# Sheet1.net
KiCad netlist of a schematic drawn in Altium Designer
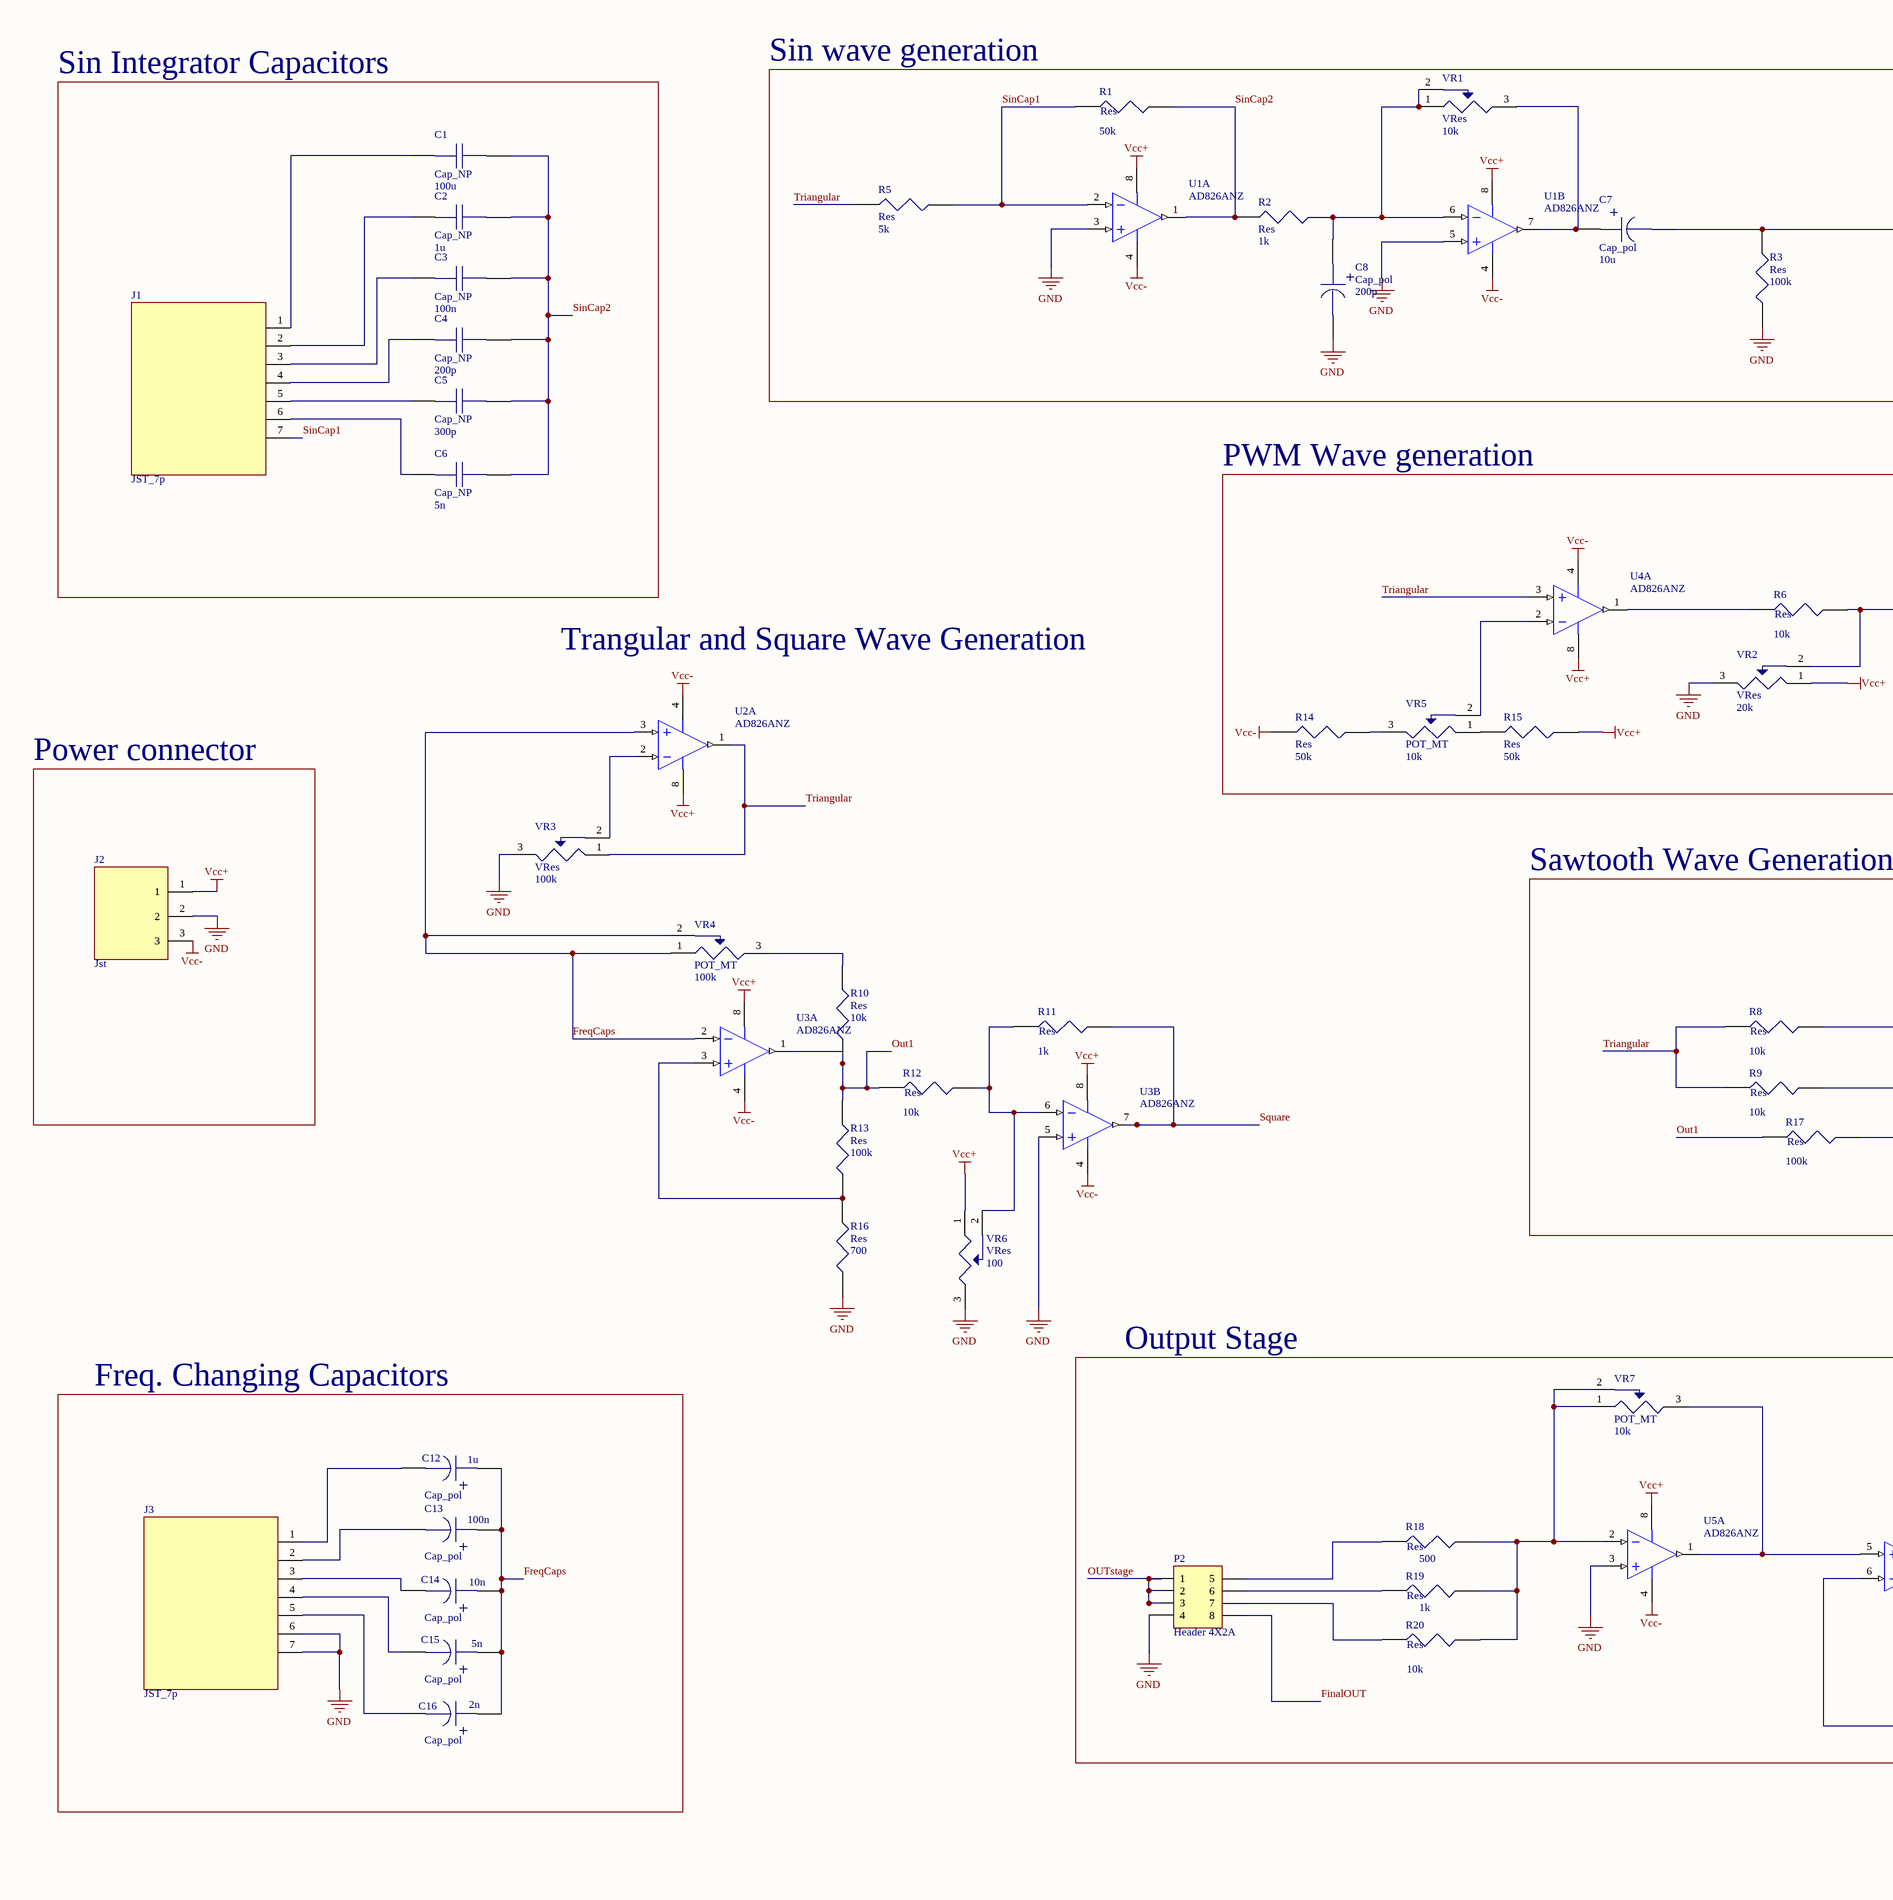
[diagram p0: Sheet1.SchDoc, left]
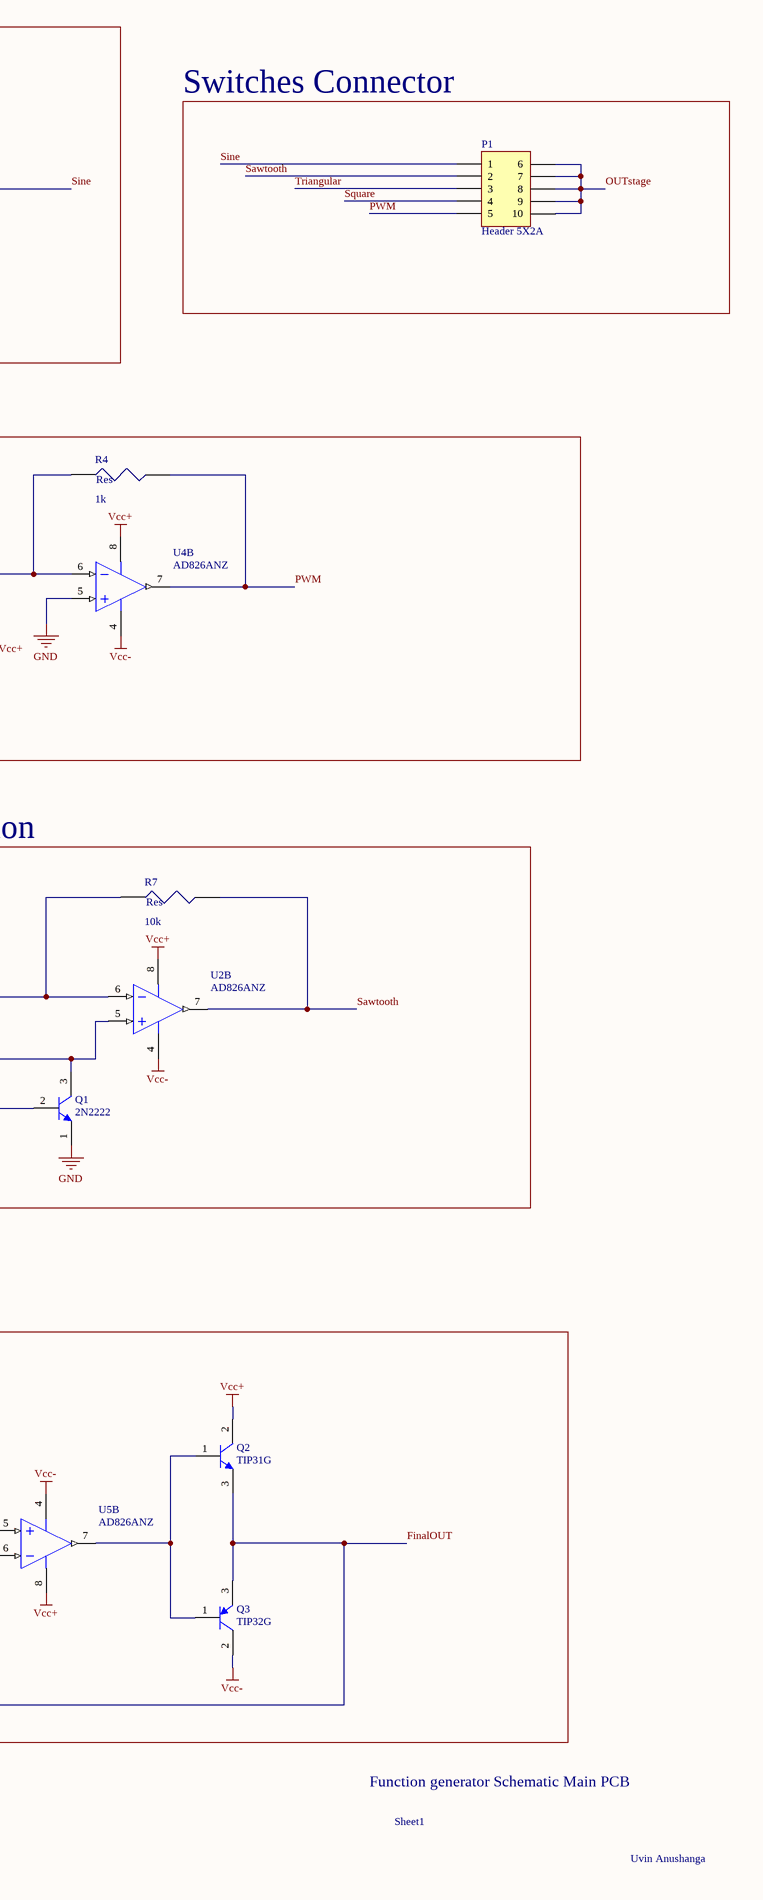
[diagram p1: Sheet1.SchDoc, right]

(export (version "E")
  (design (tool "Eeschema 10.0.6"))
  (components
    (comp (ref "C1")
      (value "Cap_NP")
      (footprint "Cap NP")
      (fields (field (name "ALTIUM_VALUE") "100u"))
      (libsource (lib "Funcgen") (part "Cap_NP"))
    )
    (comp (ref "C2")
      (value "Cap_NP")
      (footprint "Cap NP")
      (fields (field (name "ALTIUM_VALUE") "1u"))
      (libsource (lib "Funcgen") (part "Cap_NP"))
    )
    (comp (ref "C3")
      (value "Cap_NP")
      (footprint "Cap NP")
      (fields (field (name "ALTIUM_VALUE") "100n"))
      (libsource (lib "Funcgen") (part "Cap_NP"))
    )
    (comp (ref "C4")
      (value "Cap_NP")
      (footprint "Cap NP")
      (fields (field (name "ALTIUM_VALUE") "200p"))
      (libsource (lib "Funcgen") (part "Cap_NP"))
    )
    (comp (ref "C5")
      (value "Cap_NP")
      (footprint "Cap NP")
      (fields (field (name "ALTIUM_VALUE") "300p"))
      (libsource (lib "Funcgen") (part "Cap_NP"))
    )
    (comp (ref "C6")
      (value "Cap_NP")
      (footprint "Cap NP")
      (fields (field (name "ALTIUM_VALUE") "5n"))
      (libsource (lib "Funcgen") (part "Cap_NP"))
    )
    (comp (ref "C7")
      (value "Cap_pol")
      (footprint "Cap pol")
      (fields (field (name "ALTIUM_VALUE") "10u"))
      (libsource (lib "Schlib1") (part "Cap_pol"))
    )
    (comp (ref "C8")
      (value "Cap_pol")
      (footprint "Cap pol")
      (fields (field (name "ALTIUM_VALUE") "200p"))
      (libsource (lib "Schlib1") (part "Cap_pol"))
    )
    (comp (ref "C12")
      (value "Cap_pol")
      (footprint "Cap pol")
      (fields (field (name "ALTIUM_VALUE") "1u"))
      (libsource (lib "Schlib1") (part "Cap_pol"))
    )
    (comp (ref "C13")
      (value "Cap_pol")
      (footprint "Cap pol")
      (fields (field (name "ALTIUM_VALUE") "100n"))
      (libsource (lib "Schlib1") (part "Cap_pol"))
    )
    (comp (ref "C14")
      (value "Cap_pol")
      (footprint "Cap pol")
      (fields (field (name "ALTIUM_VALUE") "10n"))
      (libsource (lib "Schlib1") (part "Cap_pol"))
    )
    (comp (ref "C15")
      (value "Cap_pol")
      (footprint "Cap pol")
      (fields (field (name "ALTIUM_VALUE") "5n"))
      (libsource (lib "Schlib1") (part "Cap_pol"))
    )
    (comp (ref "C16")
      (value "Cap_pol")
      (footprint "Cap pol")
      (fields (field (name "ALTIUM_VALUE") "2n"))
      (libsource (lib "Schlib1") (part "Cap_pol"))
    )
    (comp (ref "J1") (value "JST_7p") (footprint "JST_7p") (libsource (lib "Funcgen") (part "JST_7p")))
    (comp (ref "J2") (value "Jst") (footprint "Jst_3p") (libsource (lib "Funcgen") (part "Jst_3p")))
    (comp (ref "J3") (value "JST_7p") (footprint "JST_7p") (libsource (lib "Funcgen") (part "JST_7p")))
    (comp (ref "P1")
      (value "Header 5X2A")
      (footprint "HDR2X5_CEN")
      (description "Header, 5-Pin, Dual row")
      (fields (field (name "PUBLISHER") "Altium Limited"))
      (libsource (lib "Miscellaneous Connectors") (part "Header 5X2A"))
    )
    (comp (ref "P2")
      (value "Header 4X2A")
      (footprint "HDR2X4_CEN")
      (description "Header, 4-Pin, Dual row")
      (fields (field (name "PUBLISHER") "Altium Limited"))
      (libsource (lib "Miscellaneous Connectors") (part "Header 4X2A"))
    )
    (comp (ref "Q1")
      (value "2N2222")
      (footprint "MLTC-TO-18-3")
      (description "Low Power Bipolar NPN Transistor, 30 V, -65 to 200 degC, 3-Pin TO-18, RoHS, Bulk")
      (fields (field (name "MANUFACTURER") "Multicomp"))
      (libsource (lib "Altium Content Vault") (part "BJT-NPN-EBC-3"))
    )
    (comp (ref "Q2")
      (value "TIP31G")
      (footprint "ONSC-TO-220-3-221A-09")
      (description "Complementary Silicon Plastic Power Transistor, 3-Pin TO-220, Pb-Free, Tube")
      (fields (field (name "MANUFACTURER") "On Semiconductor"))
      (libsource (lib "Altium Content Vault") (part "ONSC-NPN-B1C2E3-3_C"))
    )
    (comp (ref "Q3")
      (value "TIP32G")
      (footprint "ONSC-TO-220-3-221A-09")
      (description "Complementary Silicon Plastic Power Transistor, 3-Pin TO-220, Pb-Free, Tube")
      (fields (field (name "MANUFACTURER") "On Semiconductor"))
      (libsource (lib "Altium Content Vault") (part "ONSC-PNP-B1C2E3-3"))
    )
    (comp (ref "R1")
      (value "Res")
      (footprint "Res")
      (fields (field (name "ALTIUM_VALUE") "50k"))
      (libsource (lib "Funcgen") (part "Res"))
    )
    (comp (ref "R2")
      (value "Res")
      (footprint "Res")
      (fields (field (name "ALTIUM_VALUE") "1k"))
      (libsource (lib "Funcgen") (part "Res"))
    )
    (comp (ref "R3")
      (value "Res")
      (footprint "Res")
      (fields (field (name "ALTIUM_VALUE") "100k"))
      (libsource (lib "Funcgen") (part "Res"))
    )
    (comp (ref "R4")
      (value "Res")
      (footprint "Res")
      (fields (field (name "ALTIUM_VALUE") "1k"))
      (libsource (lib "Funcgen") (part "Res"))
    )
    (comp (ref "R5")
      (value "Res")
      (footprint "Res")
      (fields (field (name "ALTIUM_VALUE") "5k"))
      (libsource (lib "Funcgen") (part "Res"))
    )
    (comp (ref "R6")
      (value "Res")
      (footprint "Res")
      (fields (field (name "ALTIUM_VALUE") "10k"))
      (libsource (lib "Funcgen") (part "Res"))
    )
    (comp (ref "R7")
      (value "Res")
      (footprint "Res")
      (fields (field (name "ALTIUM_VALUE") "10k"))
      (libsource (lib "Funcgen") (part "Res"))
    )
    (comp (ref "R8")
      (value "Res")
      (footprint "Res")
      (fields (field (name "ALTIUM_VALUE") "10k"))
      (libsource (lib "Funcgen") (part "Res"))
    )
    (comp (ref "R9")
      (value "Res")
      (footprint "Res")
      (fields (field (name "ALTIUM_VALUE") "10k"))
      (libsource (lib "Funcgen") (part "Res"))
    )
    (comp (ref "R10")
      (value "Res")
      (footprint "Res")
      (fields (field (name "ALTIUM_VALUE") "10k"))
      (libsource (lib "Funcgen") (part "Res"))
    )
    (comp (ref "R11")
      (value "Res")
      (footprint "Res")
      (fields (field (name "ALTIUM_VALUE") "1k"))
      (libsource (lib "Funcgen") (part "Res"))
    )
    (comp (ref "R12")
      (value "Res")
      (footprint "Res")
      (fields (field (name "ALTIUM_VALUE") "10k"))
      (libsource (lib "Funcgen") (part "Res"))
    )
    (comp (ref "R13")
      (value "Res")
      (footprint "Res")
      (fields (field (name "ALTIUM_VALUE") "100k"))
      (libsource (lib "Funcgen") (part "Res"))
    )
    (comp (ref "R14")
      (value "Res")
      (footprint "Res")
      (fields (field (name "ALTIUM_VALUE") "50k"))
      (libsource (lib "Funcgen") (part "Res"))
    )
    (comp (ref "R15")
      (value "Res")
      (footprint "Res")
      (fields (field (name "ALTIUM_VALUE") "50k"))
      (libsource (lib "Funcgen") (part "Res"))
    )
    (comp (ref "R16")
      (value "Res")
      (footprint "Res")
      (fields (field (name "ALTIUM_VALUE") "700"))
      (libsource (lib "Funcgen") (part "Res"))
    )
    (comp (ref "R17")
      (value "Res")
      (footprint "Res")
      (fields (field (name "ALTIUM_VALUE") "100k"))
      (libsource (lib "Funcgen") (part "Res"))
    )
    (comp (ref "R18")
      (value "Res")
      (footprint "Res")
      (fields (field (name "ALTIUM_VALUE") "500"))
      (libsource (lib "Funcgen") (part "Res"))
    )
    (comp (ref "R19")
      (value "Res")
      (footprint "Res")
      (fields (field (name "ALTIUM_VALUE") "1k"))
      (libsource (lib "Funcgen") (part "Res"))
    )
    (comp (ref "R20")
      (value "Res")
      (footprint "Res")
      (fields (field (name "ALTIUM_VALUE") "10k"))
      (libsource (lib "Funcgen") (part "Res"))
    )
    (comp (ref "U1")
      (value "AD826ANZ")
      (footprint "ADI-N-8")
      (fields (field (name "MANUFACTURER") "Analog Devices") (field (name "GENERIC PART NUMBER") "AD826"))
      (libsource (lib "Altium Content Vault") (part "ADI-AD7xx_8xx-X-8"))
    )
    (comp (ref "U2")
      (value "AD826ANZ")
      (footprint "ADI-N-8")
      (fields (field (name "MANUFACTURER") "Analog Devices") (field (name "GENERIC PART NUMBER") "AD826"))
      (libsource (lib "Altium Content Vault") (part "ADI-AD7xx_8xx-X-8"))
    )
    (comp (ref "U3")
      (value "AD826ANZ")
      (footprint "ADI-N-8")
      (fields (field (name "MANUFACTURER") "Analog Devices") (field (name "GENERIC PART NUMBER") "AD826"))
      (libsource (lib "Altium Content Vault") (part "ADI-AD7xx_8xx-X-8"))
    )
    (comp (ref "U4")
      (value "AD826ANZ")
      (footprint "ADI-N-8")
      (fields (field (name "MANUFACTURER") "Analog Devices") (field (name "GENERIC PART NUMBER") "AD826"))
      (libsource (lib "Altium Content Vault") (part "ADI-AD7xx_8xx-X-8"))
    )
    (comp (ref "U5")
      (value "AD826ANZ")
      (footprint "ADI-N-8")
      (fields (field (name "MANUFACTURER") "Analog Devices") (field (name "GENERIC PART NUMBER") "AD826"))
      (libsource (lib "Altium Content Vault") (part "ADI-AD7xx_8xx-X-8"))
    )
    (comp (ref "VR1")
      (value "VRes")
      (footprint "VerRes")
      (fields (field (name "ALTIUM_VALUE") "10k"))
      (libsource (lib "Funcgen") (part "VRes"))
    )
    (comp (ref "VR2")
      (value "VRes")
      (footprint "VerRes")
      (fields (field (name "ALTIUM_VALUE") "20k"))
      (libsource (lib "Funcgen") (part "VRes"))
    )
    (comp (ref "VR3")
      (value "VRes")
      (footprint "VerRes")
      (fields (field (name "ALTIUM_VALUE") "100k"))
      (libsource (lib "Funcgen") (part "VRes"))
    )
    (comp (ref "VR4")
      (value "POT_MT")
      (footprint "POT MT")
      (fields (field (name "ALTIUM_VALUE") "100k"))
      (libsource (lib "Funcgen") (part "POT_MT"))
    )
    (comp (ref "VR5")
      (value "POT_MT")
      (footprint "POT MT")
      (fields (field (name "ALTIUM_VALUE") "10k"))
      (libsource (lib "Funcgen") (part "POT_MT"))
    )
    (comp (ref "VR6")
      (value "VRes")
      (footprint "VerRes")
      (fields (field (name "ALTIUM_VALUE") "100"))
      (libsource (lib "Funcgen") (part "VRes"))
    )
    (comp (ref "VR7")
      (value "POT_MT")
      (footprint "POT MT")
      (fields (field (name "ALTIUM_VALUE") "10k"))
      (libsource (lib "Funcgen") (part "POT_MT"))
    )
  )
  (nets
    (net (code "1") (name "/FinalOUT") (class "Default")
      (node (ref "P2") (pin "8") (pinfunction "8_8") (pintype "passive"))
      (node (ref "Q2") (pin "3") (pinfunction "E_3") (pintype "passive"))
      (node (ref "Q3") (pin "3") (pinfunction "E_3") (pintype "passive"))
      (node (ref "U5") (pin "6") (pinfunction "-IN_2_6") (pintype "input"))
    )
    (net (code "2") (name "/FreqCaps") (class "Default")
      (node (ref "C12") (pin "1") (pinfunction "1_1") (pintype "passive"))
      (node (ref "C13") (pin "1") (pinfunction "1_1") (pintype "passive"))
      (node (ref "C14") (pin "1") (pinfunction "1_1") (pintype "passive"))
      (node (ref "C15") (pin "1") (pinfunction "1_1") (pintype "passive"))
      (node (ref "C16") (pin "1") (pinfunction "1_1") (pintype "passive"))
      (node (ref "U2") (pin "3") (pinfunction "+IN_1_3") (pintype "input"))
      (node (ref "U3") (pin "2") (pinfunction "-IN_1_2") (pintype "input"))
      (node (ref "VR4") (pin "1") (pinfunction "1_1") (pintype "passive"))
      (node (ref "VR4") (pin "2") (pinfunction "2_2") (pintype "passive"))
    )
    (net (code "3") (name "/OUTstage") (class "Default")
      (node (ref "P1") (pin "10") (pinfunction "10_10") (pintype "passive"))
      (node (ref "P1") (pin "6") (pinfunction "6_6") (pintype "passive"))
      (node (ref "P1") (pin "7") (pinfunction "7_7") (pintype "passive"))
      (node (ref "P1") (pin "8") (pinfunction "8_8") (pintype "passive"))
      (node (ref "P1") (pin "9") (pinfunction "9_9") (pintype "passive"))
      (node (ref "P2") (pin "1") (pinfunction "1_1") (pintype "passive"))
      (node (ref "P2") (pin "2") (pinfunction "2_2") (pintype "passive"))
      (node (ref "P2") (pin "3") (pinfunction "3_3") (pintype "passive"))
    )
    (net (code "4") (name "/Out1") (class "Default")
      (node (ref "R10") (pin "2") (pinfunction "2_2") (pintype "passive"))
      (node (ref "R12") (pin "1") (pinfunction "1_1") (pintype "passive"))
      (node (ref "R13") (pin "1") (pinfunction "1_1") (pintype "passive"))
      (node (ref "R17") (pin "1") (pinfunction "1_1") (pintype "passive"))
      (node (ref "U3") (pin "1") (pinfunction "OUT_1_1") (pintype "output"))
    )
    (net (code "5") (name "/PWM") (class "Default")
      (node (ref "P1") (pin "5") (pinfunction "5_5") (pintype "passive"))
      (node (ref "R4") (pin "2") (pinfunction "2_2") (pintype "passive"))
      (node (ref "U4") (pin "7") (pinfunction "OUT_2_7") (pintype "output"))
    )
    (net (code "6") (name "/Sawtooth") (class "Default")
      (node (ref "P1") (pin "2") (pinfunction "2_2") (pintype "passive"))
      (node (ref "R7") (pin "2") (pinfunction "2_2") (pintype "passive"))
      (node (ref "U2") (pin "7") (pinfunction "OUT_2_7") (pintype "output"))
    )
    (net (code "7") (name "/SinCap1") (class "Default")
      (node (ref "J1") (pin "7") (pinfunction "7_7") (pintype "passive"))
      (node (ref "R1") (pin "1") (pinfunction "1_1") (pintype "passive"))
      (node (ref "R5") (pin "1") (pinfunction "1_1") (pintype "passive"))
      (node (ref "U1") (pin "2") (pinfunction "-IN_1_2") (pintype "input"))
    )
    (net (code "8") (name "/SinCap2") (class "Default")
      (node (ref "C1") (pin "2") (pinfunction "2_2") (pintype "passive"))
      (node (ref "C2") (pin "2") (pinfunction "2_2") (pintype "passive"))
      (node (ref "C3") (pin "2") (pinfunction "2_2") (pintype "passive"))
      (node (ref "C4") (pin "2") (pinfunction "2_2") (pintype "passive"))
      (node (ref "C5") (pin "2") (pinfunction "2_2") (pintype "passive"))
      (node (ref "C6") (pin "2") (pinfunction "2_2") (pintype "passive"))
      (node (ref "R1") (pin "2") (pinfunction "2_2") (pintype "passive"))
      (node (ref "R2") (pin "1") (pinfunction "1_1") (pintype "passive"))
      (node (ref "U1") (pin "1") (pinfunction "OUT_1_1") (pintype "output"))
    )
    (net (code "9") (name "/Sine") (class "Default")
      (node (ref "C7") (pin "2") (pinfunction "2_2") (pintype "passive"))
      (node (ref "P1") (pin "1") (pinfunction "1_1") (pintype "passive"))
      (node (ref "R3") (pin "1") (pinfunction "1_1") (pintype "passive"))
    )
    (net (code "10") (name "/Square") (class "Default")
      (node (ref "P1") (pin "4") (pinfunction "4_4") (pintype "passive"))
      (node (ref "R11") (pin "2") (pinfunction "2_2") (pintype "passive"))
      (node (ref "U3") (pin "7") (pinfunction "OUT_2_7") (pintype "output"))
    )
    (net (code "11") (name "/Triangular") (class "Default")
      (node (ref "P1") (pin "3") (pinfunction "3_3") (pintype "passive"))
      (node (ref "R5") (pin "2") (pinfunction "2_2") (pintype "passive"))
      (node (ref "R8") (pin "1") (pinfunction "1_1") (pintype "passive"))
      (node (ref "R9") (pin "1") (pinfunction "1_1") (pintype "passive"))
      (node (ref "U2") (pin "1") (pinfunction "OUT_1_1") (pintype "output"))
      (node (ref "U4") (pin "3") (pinfunction "+IN_1_3") (pintype "input"))
      (node (ref "VR3") (pin "1") (pinfunction "1_1") (pintype "passive"))
    )
    (net (code "12") (name "GND") (class "Default")
      (node (ref "C8") (pin "2") (pinfunction "2_2") (pintype "passive"))
      (node (ref "J2") (pin "2") (pinfunction "2_2") (pintype "passive"))
      (node (ref "J3") (pin "6") (pinfunction "6_6") (pintype "passive"))
      (node (ref "J3") (pin "7") (pinfunction "7_7") (pintype "passive"))
      (node (ref "P2") (pin "4") (pinfunction "4_4") (pintype "passive"))
      (node (ref "Q1") (pin "1") (pinfunction "E_1") (pintype "passive"))
      (node (ref "R16") (pin "2") (pinfunction "2_2") (pintype "passive"))
      (node (ref "R3") (pin "2") (pinfunction "2_2") (pintype "passive"))
      (node (ref "U1") (pin "3") (pinfunction "+IN_1_3") (pintype "input"))
      (node (ref "U1") (pin "5") (pinfunction "+IN_2_5") (pintype "input"))
      (node (ref "U3") (pin "5") (pinfunction "+IN_2_5") (pintype "input"))
      (node (ref "U4") (pin "5") (pinfunction "+IN_2_5") (pintype "input"))
      (node (ref "U5") (pin "3") (pinfunction "+IN_1_3") (pintype "input"))
      (node (ref "VR2") (pin "3") (pinfunction "3_3") (pintype "passive"))
      (node (ref "VR3") (pin "3") (pinfunction "3_3") (pintype "passive"))
      (node (ref "VR6") (pin "3") (pinfunction "3_3") (pintype "passive"))
    )
    (net (code "13") (name "Net-(C1-Pad1)") (class "Default")
      (node (ref "C1") (pin "1") (pinfunction "1_1") (pintype "passive"))
      (node (ref "J1") (pin "1") (pinfunction "1_1") (pintype "passive"))
    )
    (net (code "14") (name "Net-(C2-Pad1)") (class "Default")
      (node (ref "C2") (pin "1") (pinfunction "1_1") (pintype "passive"))
      (node (ref "J1") (pin "2") (pinfunction "2_2") (pintype "passive"))
    )
    (net (code "15") (name "Net-(C3-Pad1)") (class "Default")
      (node (ref "C3") (pin "1") (pinfunction "1_1") (pintype "passive"))
      (node (ref "J1") (pin "3") (pinfunction "3_3") (pintype "passive"))
    )
    (net (code "16") (name "Net-(C4-Pad1)") (class "Default")
      (node (ref "C4") (pin "1") (pinfunction "1_1") (pintype "passive"))
      (node (ref "J1") (pin "4") (pinfunction "4_4") (pintype "passive"))
    )
    (net (code "17") (name "Net-(C5-Pad1)") (class "Default")
      (node (ref "C5") (pin "1") (pinfunction "1_1") (pintype "passive"))
      (node (ref "J1") (pin "5") (pinfunction "5_5") (pintype "passive"))
    )
    (net (code "18") (name "Net-(C6-Pad1)") (class "Default")
      (node (ref "C6") (pin "1") (pinfunction "1_1") (pintype "passive"))
      (node (ref "J1") (pin "6") (pinfunction "6_6") (pintype "passive"))
    )
    (net (code "19") (name "Net-(C12-Pad2)") (class "Default")
      (node (ref "C12") (pin "2") (pinfunction "2_2") (pintype "passive"))
      (node (ref "J3") (pin "1") (pinfunction "1_1") (pintype "passive"))
    )
    (net (code "20") (name "Net-(C13-Pad2)") (class "Default")
      (node (ref "C13") (pin "2") (pinfunction "2_2") (pintype "passive"))
      (node (ref "J3") (pin "2") (pinfunction "2_2") (pintype "passive"))
    )
    (net (code "21") (name "Net-(C14-Pad2)") (class "Default")
      (node (ref "C14") (pin "2") (pinfunction "2_2") (pintype "passive"))
      (node (ref "J3") (pin "3") (pinfunction "3_3") (pintype "passive"))
    )
    (net (code "22") (name "Net-(C15-Pad2)") (class "Default")
      (node (ref "C15") (pin "2") (pinfunction "2_2") (pintype "passive"))
      (node (ref "J3") (pin "4") (pinfunction "4_4") (pintype "passive"))
    )
    (net (code "23") (name "Net-(C16-Pad2)") (class "Default")
      (node (ref "C16") (pin "2") (pinfunction "2_2") (pintype "passive"))
      (node (ref "J3") (pin "5") (pinfunction "5_5") (pintype "passive"))
    )
    (net (code "24") (name "Net-(P2-Pad5)") (class "Default")
      (node (ref "P2") (pin "5") (pinfunction "5_5") (pintype "passive"))
      (node (ref "R18") (pin "1") (pinfunction "1_1") (pintype "passive"))
    )
    (net (code "25") (name "Net-(P2-Pad6)") (class "Default")
      (node (ref "P2") (pin "6") (pinfunction "6_6") (pintype "passive"))
      (node (ref "R19") (pin "1") (pinfunction "1_1") (pintype "passive"))
    )
    (net (code "26") (name "Net-(P2-Pad7)") (class "Default")
      (node (ref "P2") (pin "7") (pinfunction "7_7") (pintype "passive"))
      (node (ref "R20") (pin "1") (pinfunction "1_1") (pintype "passive"))
    )
    (net (code "27") (name "Net-(Q1-B)") (class "Default")
      (node (ref "Q1") (pin "2") (pinfunction "B_2") (pintype "passive"))
      (node (ref "R17") (pin "2") (pinfunction "2_2") (pintype "passive"))
    )
    (net (code "28") (name "Net-(Q1-C)") (class "Default")
      (node (ref "Q1") (pin "3") (pinfunction "C_3") (pintype "passive"))
      (node (ref "R9") (pin "2") (pinfunction "2_2") (pintype "passive"))
      (node (ref "U2") (pin "5") (pinfunction "+IN_2_5") (pintype "input"))
    )
    (net (code "29") (name "Net-(Q2-B)") (class "Default")
      (node (ref "Q2") (pin "1") (pinfunction "B_1") (pintype "passive"))
      (node (ref "Q3") (pin "1") (pinfunction "B_1") (pintype "passive"))
      (node (ref "U5") (pin "7") (pinfunction "OUT_2_7") (pintype "output"))
    )
    (net (code "30") (name "Net-(R10-Pad1)") (class "Default")
      (node (ref "R10") (pin "1") (pinfunction "1_1") (pintype "passive"))
      (node (ref "VR4") (pin "3") (pinfunction "3_3") (pintype "passive"))
    )
    (net (code "31") (name "Net-(R14-Pad1)") (class "Default")
      (node (ref "R14") (pin "1") (pinfunction "1_1") (pintype "passive"))
      (node (ref "VR5") (pin "3") (pinfunction "3_3") (pintype "passive"))
    )
    (net (code "32") (name "Net-(R15-Pad2)") (class "Default")
      (node (ref "R15") (pin "2") (pinfunction "2_2") (pintype "passive"))
      (node (ref "VR5") (pin "1") (pinfunction "1_1") (pintype "passive"))
    )
    (net (code "33") (name "Net-(U1B--IN_2)") (class "Default")
      (node (ref "C8") (pin "1") (pinfunction "1_1") (pintype "passive"))
      (node (ref "R2") (pin "2") (pinfunction "2_2") (pintype "passive"))
      (node (ref "U1") (pin "6") (pinfunction "-IN_2_6") (pintype "input"))
      (node (ref "VR1") (pin "1") (pinfunction "1_1") (pintype "passive"))
      (node (ref "VR1") (pin "2") (pinfunction "2_2") (pintype "passive"))
    )
    (net (code "34") (name "Net-(U1B-OUT_2)") (class "Default")
      (node (ref "C7") (pin "1") (pinfunction "1_1") (pintype "passive"))
      (node (ref "U1") (pin "7") (pinfunction "OUT_2_7") (pintype "output"))
      (node (ref "VR1") (pin "3") (pinfunction "3_3") (pintype "passive"))
    )
    (net (code "35") (name "Net-(U2A--IN_1)") (class "Default")
      (node (ref "U2") (pin "2") (pinfunction "-IN_1_2") (pintype "input"))
      (node (ref "VR3") (pin "2") (pinfunction "2_2") (pintype "passive"))
    )
    (net (code "36") (name "Net-(U2B--IN_2)") (class "Default")
      (node (ref "R7") (pin "1") (pinfunction "1_1") (pintype "passive"))
      (node (ref "R8") (pin "2") (pinfunction "2_2") (pintype "passive"))
      (node (ref "U2") (pin "6") (pinfunction "-IN_2_6") (pintype "input"))
    )
    (net (code "37") (name "Net-(U3A-+IN_1)") (class "Default")
      (node (ref "R13") (pin "2") (pinfunction "2_2") (pintype "passive"))
      (node (ref "R16") (pin "1") (pinfunction "1_1") (pintype "passive"))
      (node (ref "U3") (pin "3") (pinfunction "+IN_1_3") (pintype "input"))
    )
    (net (code "38") (name "Net-(U3B--IN_2)") (class "Default")
      (node (ref "R11") (pin "1") (pinfunction "1_1") (pintype "passive"))
      (node (ref "R12") (pin "2") (pinfunction "2_2") (pintype "passive"))
      (node (ref "U3") (pin "6") (pinfunction "-IN_2_6") (pintype "input"))
      (node (ref "VR6") (pin "2") (pinfunction "2_2") (pintype "passive"))
    )
    (net (code "39") (name "Net-(U4A--IN_1)") (class "Default")
      (node (ref "U4") (pin "2") (pinfunction "-IN_1_2") (pintype "input"))
      (node (ref "VR5") (pin "2") (pinfunction "2_2") (pintype "passive"))
    )
    (net (code "40") (name "Net-(U4A-OUT_1)") (class "Default")
      (node (ref "R6") (pin "1") (pinfunction "1_1") (pintype "passive"))
      (node (ref "U4") (pin "1") (pinfunction "OUT_1_1") (pintype "output"))
    )
    (net (code "41") (name "Net-(U4B--IN_2)") (class "Default")
      (node (ref "R4") (pin "1") (pinfunction "1_1") (pintype "passive"))
      (node (ref "R6") (pin "2") (pinfunction "2_2") (pintype "passive"))
      (node (ref "U4") (pin "6") (pinfunction "-IN_2_6") (pintype "input"))
      (node (ref "VR2") (pin "2") (pinfunction "2_2") (pintype "passive"))
    )
    (net (code "42") (name "Net-(U5A--IN_1)") (class "Default")
      (node (ref "R18") (pin "2") (pinfunction "2_2") (pintype "passive"))
      (node (ref "R19") (pin "2") (pinfunction "2_2") (pintype "passive"))
      (node (ref "R20") (pin "2") (pinfunction "2_2") (pintype "passive"))
      (node (ref "U5") (pin "2") (pinfunction "-IN_1_2") (pintype "input"))
      (node (ref "VR7") (pin "1") (pinfunction "1_1") (pintype "passive"))
      (node (ref "VR7") (pin "2") (pinfunction "2_2") (pintype "passive"))
    )
    (net (code "43") (name "Net-(U5A-OUT_1)") (class "Default")
      (node (ref "U5") (pin "1") (pinfunction "OUT_1_1") (pintype "output"))
      (node (ref "U5") (pin "5") (pinfunction "+IN_2_5") (pintype "input"))
      (node (ref "VR7") (pin "3") (pinfunction "3_3") (pintype "passive"))
    )
    (net (code "44") (name "Vcc+") (class "Default")
      (node (ref "J2") (pin "1") (pinfunction "1_1") (pintype "passive"))
      (node (ref "Q2") (pin "2") (pinfunction "C_2") (pintype "passive"))
      (node (ref "R15") (pin "1") (pinfunction "1_1") (pintype "passive"))
      (node (ref "U1") (pin "8") (pinfunction "+V_8") (pintype "power_in"))
      (node (ref "U2") (pin "8") (pinfunction "+V_8") (pintype "power_in"))
      (node (ref "U3") (pin "8") (pinfunction "+V_8") (pintype "power_in"))
      (node (ref "U4") (pin "8") (pinfunction "+V_8") (pintype "power_in"))
      (node (ref "U5") (pin "8") (pinfunction "+V_8") (pintype "power_in"))
      (node (ref "VR2") (pin "1") (pinfunction "1_1") (pintype "passive"))
      (node (ref "VR6") (pin "1") (pinfunction "1_1") (pintype "passive"))
    )
    (net (code "45") (name "Vcc-") (class "Default")
      (node (ref "J2") (pin "3") (pinfunction "3_3") (pintype "passive"))
      (node (ref "Q3") (pin "2") (pinfunction "C_2") (pintype "passive"))
      (node (ref "R14") (pin "2") (pinfunction "2_2") (pintype "passive"))
      (node (ref "U1") (pin "4") (pinfunction "-V_4") (pintype "power_in"))
      (node (ref "U2") (pin "4") (pinfunction "-V_4") (pintype "power_in"))
      (node (ref "U3") (pin "4") (pinfunction "-V_4") (pintype "power_in"))
      (node (ref "U4") (pin "4") (pinfunction "-V_4") (pintype "power_in"))
      (node (ref "U5") (pin "4") (pinfunction "-V_4") (pintype "power_in"))
    )
  )
)
